# manhole.net
KiCad netlist of a schematic drawn in EAGLE
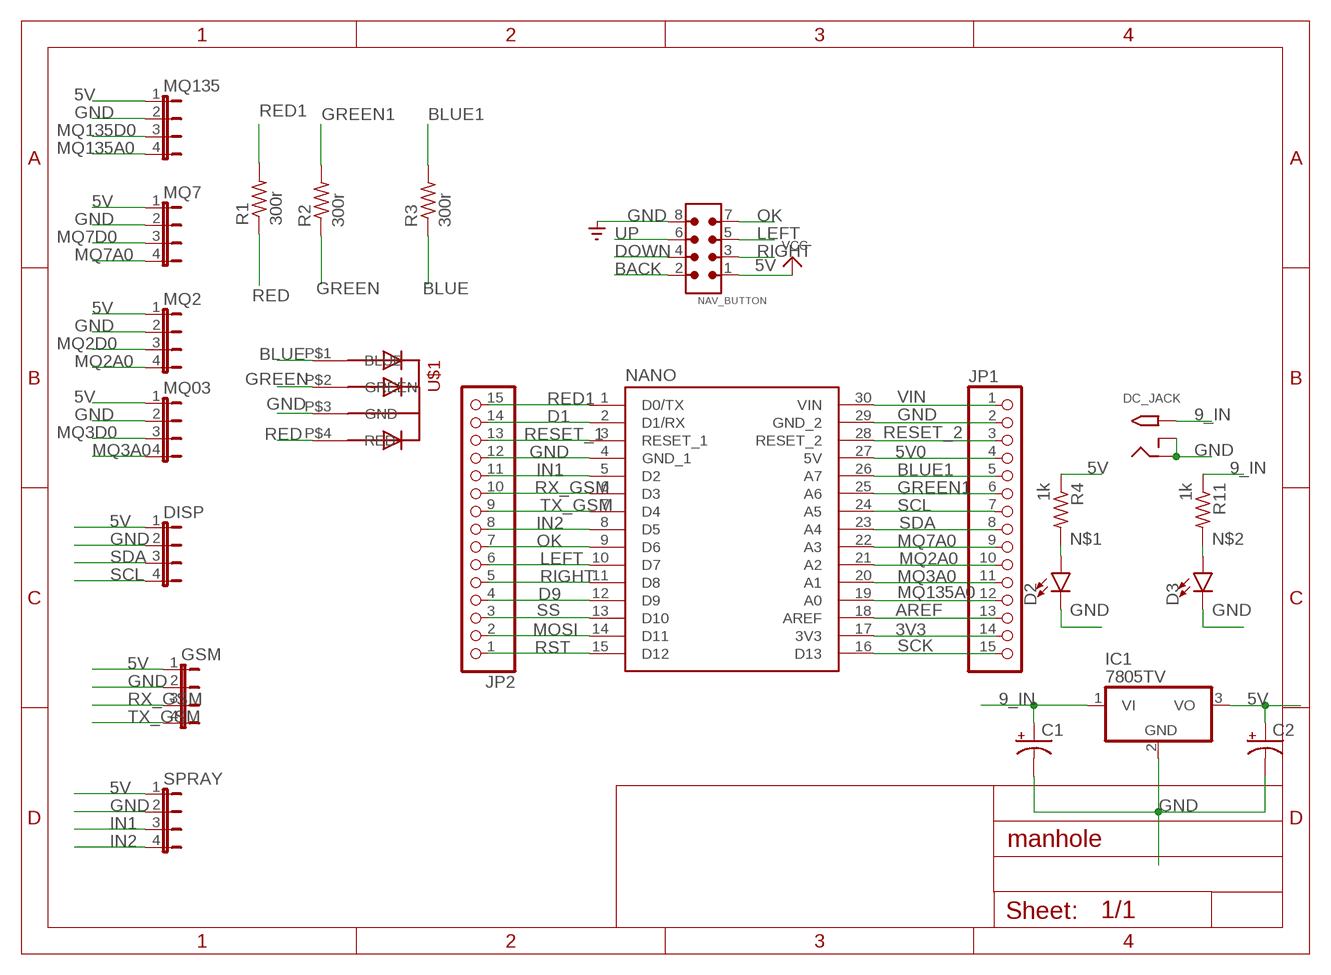
[diagram p0: schematic, sheet 1]

(export (version "E")
  (design (tool "Eeschema 10.0.6"))
  (components
    (comp (ref "C1")
      (value "CPOL-USE3.5-8")
      (footprint "eagle-import:E3,5-8")
      (libsource (lib "eagle-import") (part "CPOL-USE3.5-8"))
    )
    (comp (ref "C2")
      (value "CPOL-USE3.5-8")
      (footprint "eagle-import:E3,5-8")
      (libsource (lib "eagle-import") (part "CPOL-USE3.5-8"))
    )
    (comp (ref "D2")
      (value "LED3MM")
      (footprint "eagle-import:LED_3MM")
      (libsource (lib "eagle-import") (part "LED3MM"))
    )
    (comp (ref "D3")
      (value "LED3MM")
      (footprint "eagle-import:LED_3MM")
      (libsource (lib "eagle-import") (part "LED3MM"))
    )
    (comp (ref "DC_JACK")
      (value "2.1MMJACKTHM")
      (footprint "eagle-import:PJ-102A")
      (libsource (lib "eagle-import") (part "2.1MMJACKTHM"))
    )
    (comp (ref "DISP")
      (value "JP4E")
      (footprint "eagle-import:JP4")
      (libsource (lib "eagle-import") (part "JP4E"))
    )
    (comp (ref "GSM")
      (value "JP4E")
      (footprint "eagle-import:JP4")
      (libsource (lib "eagle-import") (part "JP4E"))
    )
    (comp (ref "IC1")
      (value "7805TV")
      (footprint "eagle-import:TO220V")
      (libsource (lib "eagle-import") (part "78TV05"))
    )
    (comp (ref "JP1")
      (value "PINHD-1X15")
      (footprint "eagle-import:1X15")
      (libsource (lib "eagle-import") (part "PINHD-1X15"))
    )
    (comp (ref "JP2")
      (value "PINHD-1X15")
      (footprint "eagle-import:1X15")
      (libsource (lib "eagle-import") (part "PINHD-1X15"))
    )
    (comp (ref "MQ2")
      (value "JP4E")
      (footprint "eagle-import:JP4")
      (libsource (lib "eagle-import") (part "JP4E"))
    )
    (comp (ref "MQ03")
      (value "JP4E")
      (footprint "eagle-import:JP4")
      (libsource (lib "eagle-import") (part "JP4E"))
    )
    (comp (ref "MQ7")
      (value "JP4E")
      (footprint "eagle-import:JP4")
      (libsource (lib "eagle-import") (part "JP4E"))
    )
    (comp (ref "MQ135")
      (value "JP4E")
      (footprint "eagle-import:JP4")
      (libsource (lib "eagle-import") (part "JP4E"))
    )
    (comp (ref "NANO")
      (value "A000005")
      (footprint "eagle-import:MODULE_A000005")
      (fields (field (name "MF") "Arduino"))
      (libsource (lib "eagle-import") (part "A000005"))
    )
    (comp (ref "NAV_BUTTON")
      (value "6120XX21621_61200821621")
      (footprint "eagle-import:61200821621")
      (libsource (lib "eagle-import") (part "6120XX21621_61200821621"))
    )
    (comp (ref "R1")
      (value "300r")
      (footprint "eagle-import:M0805")
      (libsource (lib "eagle-import") (part "R-US_M0805"))
    )
    (comp (ref "R2")
      (value "300r")
      (footprint "eagle-import:M0805")
      (libsource (lib "eagle-import") (part "R-US_M0805"))
    )
    (comp (ref "R3")
      (value "300r")
      (footprint "eagle-import:M0805")
      (libsource (lib "eagle-import") (part "R-US_M0805"))
    )
    (comp (ref "R4")
      (value "1k")
      (footprint "eagle-import:M0805")
      (libsource (lib "eagle-import") (part "R-US_M0805"))
    )
    (comp (ref "R11")
      (value "1k")
      (footprint "eagle-import:M0805")
      (libsource (lib "eagle-import") (part "R-US_M0805"))
    )
    (comp (ref "SPRAY")
      (value "JP4E")
      (footprint "eagle-import:JP4")
      (libsource (lib "eagle-import") (part "JP4E"))
    )
    (comp (ref "U$1")
      (value "5MMRGBLED")
      (footprint "eagle-import:LED5MMRGB")
      (libsource (lib "eagle-import") (part "5MMRGBLED"))
    )
  )
  (nets
    (net (code "1") (name "/3V3") (class "Default")
      (node (ref "JP1") (pin "14") (pinfunction "14_14") (pintype "passive"))
      (node (ref "NANO") (pin "17") (pinfunction "3V3_17") (pintype "power_in"))
    )
    (net (code "2") (name "/5V0") (class "Default")
      (node (ref "JP1") (pin "4") (pinfunction "4_4") (pintype "passive"))
      (node (ref "NANO") (pin "27") (pinfunction "5V_27") (pintype "power_in"))
    )
    (net (code "3") (name "/9_IN") (class "Default")
      (node (ref "C1") (pin "+") (pinfunction "+_+") (pintype "passive"))
      (node (ref "DC_JACK") (pin "TIP") (pinfunction "TIP_TIP") (pintype "bidirectional"))
      (node (ref "IC1") (pin "1") (pinfunction "VI_1") (pintype "input"))
      (node (ref "R11") (pin "1") (pinfunction "1_1") (pintype "passive"))
    )
    (net (code "4") (name "/AREF") (class "Default")
      (node (ref "JP1") (pin "13") (pinfunction "13_13") (pintype "passive"))
      (node (ref "NANO") (pin "18") (pinfunction "AREF_18") (pintype "input"))
    )
    (net (code "5") (name "/BACK") (class "Default")
      (node (ref "NAV_BUTTON") (pin "2") (pinfunction "2_2") (pintype "passive"))
    )
    (net (code "6") (name "/BLUE") (class "Default")
      (node (ref "R3") (pin "1") (pinfunction "1_1") (pintype "passive"))
      (node (ref "U$1") (pin "P$1") (pinfunction "BLUE_P$1") (pintype "bidirectional"))
    )
    (net (code "7") (name "/BLUE1") (class "Default")
      (node (ref "JP1") (pin "5") (pinfunction "5_5") (pintype "passive"))
      (node (ref "NANO") (pin "26") (pinfunction "A7_26") (pintype "input"))
      (node (ref "R3") (pin "2") (pinfunction "2_2") (pintype "passive"))
    )
    (net (code "8") (name "/D1") (class "Default")
      (node (ref "JP2") (pin "14") (pinfunction "14_14") (pintype "passive"))
      (node (ref "NANO") (pin "2") (pinfunction "D1/RX_2") (pintype "bidirectional"))
    )
    (net (code "9") (name "/D9") (class "Default")
      (node (ref "JP2") (pin "4") (pinfunction "4_4") (pintype "passive"))
      (node (ref "NANO") (pin "12") (pinfunction "D9_12") (pintype "bidirectional"))
    )
    (net (code "10") (name "/DOWN") (class "Default")
      (node (ref "NAV_BUTTON") (pin "4") (pinfunction "4_4") (pintype "passive"))
    )
    (net (code "11") (name "/GREEN") (class "Default")
      (node (ref "R2") (pin "1") (pinfunction "1_1") (pintype "passive"))
      (node (ref "U$1") (pin "P$2") (pinfunction "GREEN_P$2") (pintype "bidirectional"))
    )
    (net (code "12") (name "/GREEN1") (class "Default")
      (node (ref "JP1") (pin "6") (pinfunction "6_6") (pintype "passive"))
      (node (ref "NANO") (pin "25") (pinfunction "A6_25") (pintype "input"))
      (node (ref "R2") (pin "2") (pinfunction "2_2") (pintype "passive"))
    )
    (net (code "13") (name "/IN1") (class "Default")
      (node (ref "JP2") (pin "11") (pinfunction "11_11") (pintype "passive"))
      (node (ref "NANO") (pin "5") (pinfunction "D2_5") (pintype "bidirectional"))
      (node (ref "SPRAY") (pin "3") (pinfunction "3_3") (pintype "passive"))
    )
    (net (code "14") (name "/IN2") (class "Default")
      (node (ref "JP2") (pin "8") (pinfunction "8_8") (pintype "passive"))
      (node (ref "NANO") (pin "8") (pinfunction "D5_8") (pintype "bidirectional"))
      (node (ref "SPRAY") (pin "4") (pinfunction "4_4") (pintype "passive"))
    )
    (net (code "15") (name "/LEFT") (class "Default")
      (node (ref "JP2") (pin "6") (pinfunction "6_6") (pintype "passive"))
      (node (ref "NANO") (pin "10") (pinfunction "D7_10") (pintype "bidirectional"))
      (node (ref "NAV_BUTTON") (pin "5") (pinfunction "5_5") (pintype "passive"))
    )
    (net (code "16") (name "/MOSI") (class "Default")
      (node (ref "JP2") (pin "2") (pinfunction "2_2") (pintype "passive"))
      (node (ref "NANO") (pin "14") (pinfunction "D11_14") (pintype "bidirectional"))
    )
    (net (code "17") (name "/MQ2A0") (class "Default")
      (node (ref "JP1") (pin "10") (pinfunction "10_10") (pintype "passive"))
      (node (ref "MQ2") (pin "4") (pinfunction "4_4") (pintype "passive"))
      (node (ref "NANO") (pin "21") (pinfunction "A2_21") (pintype "input"))
    )
    (net (code "18") (name "/MQ2D0") (class "Default")
      (node (ref "MQ2") (pin "3") (pinfunction "3_3") (pintype "passive"))
    )
    (net (code "19") (name "/MQ3A0") (class "Default")
      (node (ref "JP1") (pin "11") (pinfunction "11_11") (pintype "passive"))
      (node (ref "MQ03") (pin "4") (pinfunction "4_4") (pintype "passive"))
      (node (ref "NANO") (pin "20") (pinfunction "A1_20") (pintype "input"))
    )
    (net (code "20") (name "/MQ3D0") (class "Default")
      (node (ref "MQ03") (pin "3") (pinfunction "3_3") (pintype "passive"))
    )
    (net (code "21") (name "/MQ7A0") (class "Default")
      (node (ref "JP1") (pin "9") (pinfunction "9_9") (pintype "passive"))
      (node (ref "MQ7") (pin "4") (pinfunction "4_4") (pintype "passive"))
      (node (ref "NANO") (pin "22") (pinfunction "A3_22") (pintype "input"))
    )
    (net (code "22") (name "/MQ7D0") (class "Default")
      (node (ref "MQ7") (pin "3") (pinfunction "3_3") (pintype "passive"))
    )
    (net (code "23") (name "/MQ135A0") (class "Default")
      (node (ref "JP1") (pin "12") (pinfunction "12_12") (pintype "passive"))
      (node (ref "MQ135") (pin "4") (pinfunction "4_4") (pintype "passive"))
      (node (ref "NANO") (pin "19") (pinfunction "A0_19") (pintype "input"))
    )
    (net (code "24") (name "/MQ135D0") (class "Default")
      (node (ref "MQ135") (pin "3") (pinfunction "3_3") (pintype "passive"))
    )
    (net (code "25") (name "/N$1") (class "Default")
      (node (ref "D2") (pin "A") (pinfunction "A_A") (pintype "passive"))
      (node (ref "R4") (pin "2") (pinfunction "2_2") (pintype "passive"))
    )
    (net (code "26") (name "/N$2") (class "Default")
      (node (ref "D3") (pin "A") (pinfunction "A_A") (pintype "passive"))
      (node (ref "R11") (pin "2") (pinfunction "2_2") (pintype "passive"))
    )
    (net (code "27") (name "/OK") (class "Default")
      (node (ref "JP2") (pin "7") (pinfunction "7_7") (pintype "passive"))
      (node (ref "NANO") (pin "9") (pinfunction "D6_9") (pintype "bidirectional"))
      (node (ref "NAV_BUTTON") (pin "7") (pinfunction "7_7") (pintype "passive"))
    )
    (net (code "28") (name "/RED") (class "Default")
      (node (ref "R1") (pin "1") (pinfunction "1_1") (pintype "passive"))
      (node (ref "U$1") (pin "P$4") (pinfunction "RED_P$4") (pintype "bidirectional"))
    )
    (net (code "29") (name "/RED1") (class "Default")
      (node (ref "JP2") (pin "15") (pinfunction "15_15") (pintype "passive"))
      (node (ref "NANO") (pin "1") (pinfunction "D0/TX_1") (pintype "bidirectional"))
      (node (ref "R1") (pin "2") (pinfunction "2_2") (pintype "passive"))
    )
    (net (code "30") (name "/RESET_1") (class "Default")
      (node (ref "JP2") (pin "13") (pinfunction "13_13") (pintype "passive"))
      (node (ref "NANO") (pin "3") (pinfunction "RESET_1_3") (pintype "input"))
    )
    (net (code "31") (name "/RESET_2") (class "Default")
      (node (ref "JP1") (pin "3") (pinfunction "3_3") (pintype "passive"))
      (node (ref "NANO") (pin "28") (pinfunction "RESET_2_28") (pintype "input"))
    )
    (net (code "32") (name "/RIGHT") (class "Default")
      (node (ref "JP2") (pin "5") (pinfunction "5_5") (pintype "passive"))
      (node (ref "NANO") (pin "11") (pinfunction "D8_11") (pintype "bidirectional"))
      (node (ref "NAV_BUTTON") (pin "3") (pinfunction "3_3") (pintype "passive"))
    )
    (net (code "33") (name "/RST") (class "Default")
      (node (ref "JP2") (pin "1") (pinfunction "1_1") (pintype "passive"))
      (node (ref "NANO") (pin "15") (pinfunction "D12_15") (pintype "bidirectional"))
    )
    (net (code "34") (name "/RX_GSM") (class "Default")
      (node (ref "GSM") (pin "3") (pinfunction "3_3") (pintype "passive"))
      (node (ref "JP2") (pin "10") (pinfunction "10_10") (pintype "passive"))
      (node (ref "NANO") (pin "6") (pinfunction "D3_6") (pintype "bidirectional"))
    )
    (net (code "35") (name "/SCK") (class "Default")
      (node (ref "JP1") (pin "15") (pinfunction "15_15") (pintype "passive"))
      (node (ref "NANO") (pin "16") (pinfunction "D13_16") (pintype "bidirectional"))
    )
    (net (code "36") (name "/SCL") (class "Default")
      (node (ref "DISP") (pin "4") (pinfunction "4_4") (pintype "passive"))
      (node (ref "JP1") (pin "7") (pinfunction "7_7") (pintype "passive"))
      (node (ref "NANO") (pin "24") (pinfunction "A5_24") (pintype "input"))
    )
    (net (code "37") (name "/SDA") (class "Default")
      (node (ref "DISP") (pin "3") (pinfunction "3_3") (pintype "passive"))
      (node (ref "JP1") (pin "8") (pinfunction "8_8") (pintype "passive"))
      (node (ref "NANO") (pin "23") (pinfunction "A4_23") (pintype "input"))
    )
    (net (code "38") (name "/SS") (class "Default")
      (node (ref "JP2") (pin "3") (pinfunction "3_3") (pintype "passive"))
      (node (ref "NANO") (pin "13") (pinfunction "D10_13") (pintype "bidirectional"))
    )
    (net (code "39") (name "/TX_GSM") (class "Default")
      (node (ref "GSM") (pin "4") (pinfunction "4_4") (pintype "passive"))
      (node (ref "JP2") (pin "9") (pinfunction "9_9") (pintype "passive"))
      (node (ref "NANO") (pin "7") (pinfunction "D4_7") (pintype "bidirectional"))
    )
    (net (code "40") (name "/UP") (class "Default")
      (node (ref "NAV_BUTTON") (pin "6") (pinfunction "6_6") (pintype "passive"))
    )
    (net (code "41") (name "/VIN") (class "Default")
      (node (ref "JP1") (pin "1") (pinfunction "1_1") (pintype "passive"))
      (node (ref "NANO") (pin "30") (pinfunction "VIN_30") (pintype "power_in"))
    )
    (net (code "42") (name "SUPPLY0_GND_") (class "Default")
      (node (ref "C1") (pin "-") (pinfunction "-_-") (pintype "passive"))
      (node (ref "C2") (pin "-") (pinfunction "-_-") (pintype "passive"))
      (node (ref "D2") (pin "K") (pinfunction "C_K") (pintype "passive"))
      (node (ref "D3") (pin "K") (pinfunction "C_K") (pintype "passive"))
      (node (ref "DC_JACK") (pin "RING") (pinfunction "RING_RING") (pintype "bidirectional"))
      (node (ref "DC_JACK") (pin "RING_SW") (pinfunction "RING_SW_RING_SW") (pintype "bidirectional"))
      (node (ref "DISP") (pin "2") (pinfunction "2_2") (pintype "passive"))
      (node (ref "GSM") (pin "2") (pinfunction "2_2") (pintype "passive"))
      (node (ref "IC1") (pin "2") (pinfunction "GND_2") (pintype "passive"))
      (node (ref "JP1") (pin "2") (pinfunction "2_2") (pintype "passive"))
      (node (ref "JP2") (pin "12") (pinfunction "12_12") (pintype "passive"))
      (node (ref "MQ03") (pin "2") (pinfunction "2_2") (pintype "passive"))
      (node (ref "MQ135") (pin "2") (pinfunction "2_2") (pintype "passive"))
      (node (ref "MQ2") (pin "2") (pinfunction "2_2") (pintype "passive"))
      (node (ref "MQ7") (pin "2") (pinfunction "2_2") (pintype "passive"))
      (node (ref "NANO") (pin "29") (pinfunction "GND_2_29") (pintype "power_in"))
      (node (ref "NANO") (pin "4") (pinfunction "GND_1_4") (pintype "power_in"))
      (node (ref "NAV_BUTTON") (pin "8") (pinfunction "8_8") (pintype "passive"))
      (node (ref "SPRAY") (pin "2") (pinfunction "2_2") (pintype "passive"))
      (node (ref "U$1") (pin "P$3") (pinfunction "GND_P$3") (pintype "bidirectional"))
    )
    (net (code "43") (name "VCC") (class "Default")
      (node (ref "C2") (pin "+") (pinfunction "+_+") (pintype "passive"))
      (node (ref "DISP") (pin "1") (pinfunction "1_1") (pintype "passive"))
      (node (ref "GSM") (pin "1") (pinfunction "1_1") (pintype "passive"))
      (node (ref "IC1") (pin "3") (pinfunction "VO_3") (pintype "passive"))
      (node (ref "MQ03") (pin "1") (pinfunction "1_1") (pintype "passive"))
      (node (ref "MQ135") (pin "1") (pinfunction "1_1") (pintype "passive"))
      (node (ref "MQ2") (pin "1") (pinfunction "1_1") (pintype "passive"))
      (node (ref "MQ7") (pin "1") (pinfunction "1_1") (pintype "passive"))
      (node (ref "NAV_BUTTON") (pin "1") (pinfunction "1_1") (pintype "passive"))
      (node (ref "R4") (pin "1") (pinfunction "1_1") (pintype "passive"))
      (node (ref "SPRAY") (pin "1") (pinfunction "1_1") (pintype "passive"))
    )
  )
)
